# Amplifier.net
KiCad netlist of a schematic drawn in Altium Designer
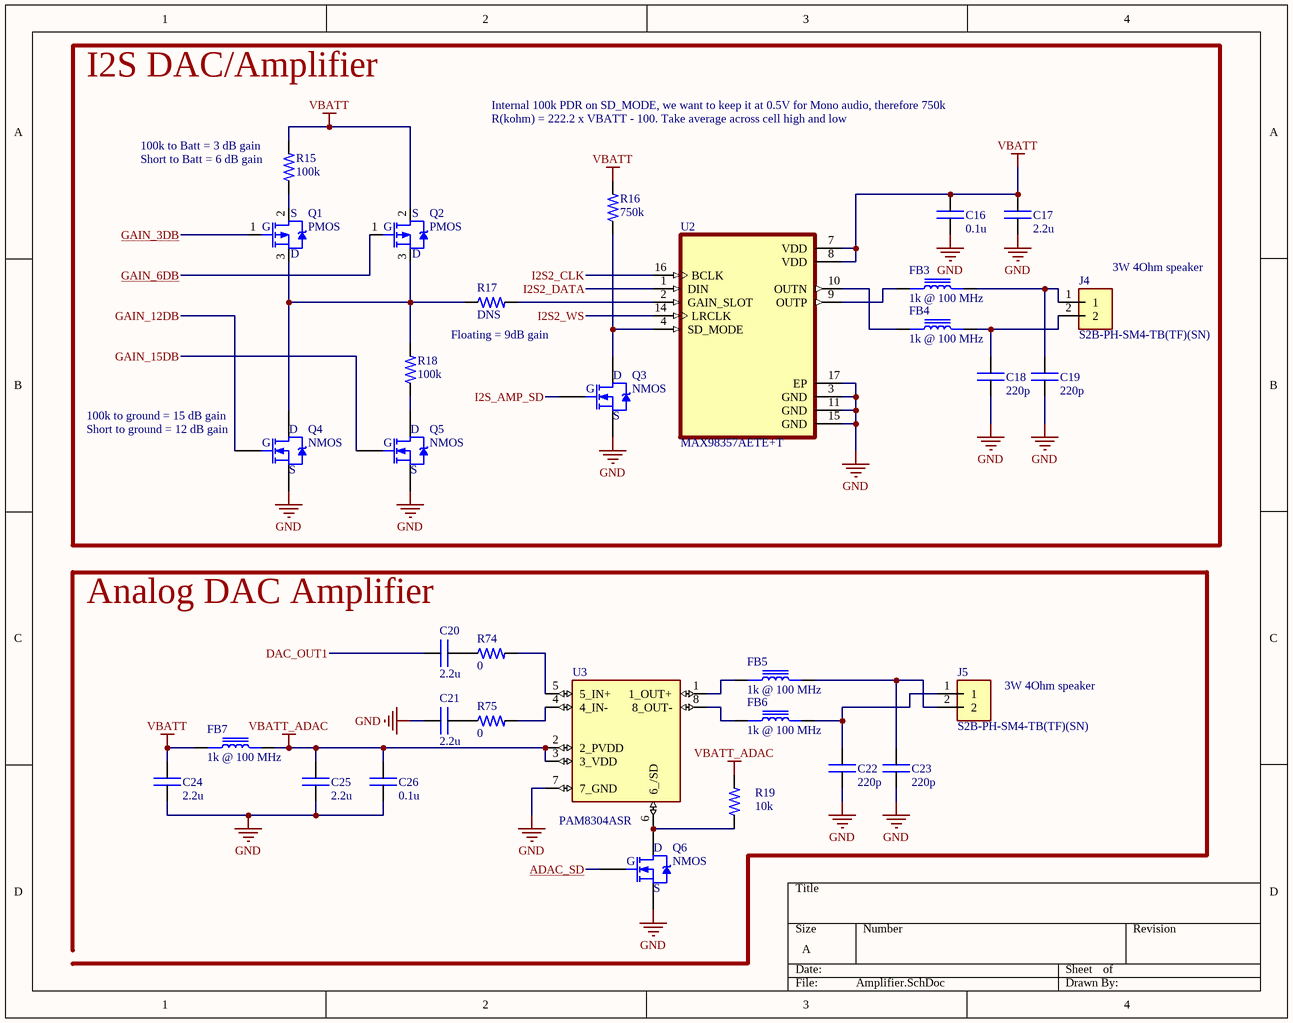
[diagram p0: Amplifier.SchDoc]

(export (version "E")
  (design (tool "Eeschema 10.0.6"))
  (components
    (comp (ref "C16")
      (value "0.1u")
      (footprint "Christmas-2023_Soundboard:0603-CAP")
      (description "Capaicitor")
      (fields (field (name "Comment") "CAP"))
      (libsource (lib "Christmas-2023_Soundboard") (part "CAP"))
    )
    (comp (ref "C17")
      (value "2.2u")
      (footprint "Christmas-2023_Soundboard:0603-CAP")
      (description "Capaicitor")
      (fields (field (name "Comment") "CAP"))
      (libsource (lib "Christmas-2023_Soundboard") (part "CAP"))
    )
    (comp (ref "C18")
      (value "220p")
      (footprint "Christmas-2023_Soundboard:0603-CAP")
      (description "Capaicitor")
      (fields (field (name "Comment") "CAP"))
      (libsource (lib "Christmas-2023_Soundboard") (part "CAP"))
    )
    (comp (ref "C19")
      (value "220p")
      (footprint "Christmas-2023_Soundboard:0603-CAP")
      (description "Capaicitor")
      (fields (field (name "Comment") "CAP"))
      (libsource (lib "Christmas-2023_Soundboard") (part "CAP"))
    )
    (comp (ref "C20")
      (value "2.2u")
      (footprint "Christmas-2023_Soundboard:0603-CAP")
      (description "Capaicitor")
      (fields (field (name "Comment") "CAP"))
      (libsource (lib "Christmas-2023_Soundboard") (part "CAP"))
    )
    (comp (ref "C21")
      (value "2.2u")
      (footprint "Christmas-2023_Soundboard:0603-CAP")
      (description "Capaicitor")
      (fields (field (name "Comment") "CAP"))
      (libsource (lib "Christmas-2023_Soundboard") (part "CAP"))
    )
    (comp (ref "C22")
      (value "220p")
      (footprint "Christmas-2023_Soundboard:0603-CAP")
      (description "Capaicitor")
      (fields (field (name "Comment") "CAP"))
      (libsource (lib "Christmas-2023_Soundboard") (part "CAP"))
    )
    (comp (ref "C23")
      (value "220p")
      (footprint "Christmas-2023_Soundboard:0603-CAP")
      (description "Capaicitor")
      (fields (field (name "Comment") "CAP"))
      (libsource (lib "Christmas-2023_Soundboard") (part "CAP"))
    )
    (comp (ref "C24")
      (value "2.2u")
      (footprint "Christmas-2023_Soundboard:0603-CAP")
      (description "Capaicitor")
      (fields (field (name "Comment") "CAP"))
      (libsource (lib "Christmas-2023_Soundboard") (part "CAP"))
    )
    (comp (ref "C25")
      (value "2.2u")
      (footprint "Christmas-2023_Soundboard:0603-CAP")
      (description "Capaicitor")
      (fields (field (name "Comment") "CAP"))
      (libsource (lib "Christmas-2023_Soundboard") (part "CAP"))
    )
    (comp (ref "C26")
      (value "0.1u")
      (footprint "Christmas-2023_Soundboard:0603-CAP")
      (description "Capaicitor")
      (fields (field (name "Comment") "CAP"))
      (libsource (lib "Christmas-2023_Soundboard") (part "CAP"))
    )
    (comp (ref "FB3")
      (value "1k @ 100 MHz")
      (footprint "Christmas-2023_Soundboard:0603-FB")
      (fields (field (name "MFR") "TDK"))
      (libsource (lib "Christmas-2023_Soundboard") (part "FERRITE BEAD"))
    )
    (comp (ref "FB4")
      (value "1k @ 100 MHz")
      (footprint "Christmas-2023_Soundboard:0603-FB")
      (fields (field (name "MFR") "TDK"))
      (libsource (lib "Christmas-2023_Soundboard") (part "FERRITE BEAD"))
    )
    (comp (ref "FB5")
      (value "1k @ 100 MHz")
      (footprint "Christmas-2023_Soundboard:0603-FB")
      (fields (field (name "MFR") "TDK"))
      (libsource (lib "Christmas-2023_Soundboard") (part "FERRITE BEAD"))
    )
    (comp (ref "FB6")
      (value "1k @ 100 MHz")
      (footprint "Christmas-2023_Soundboard:0603-FB")
      (fields (field (name "MFR") "TDK"))
      (libsource (lib "Christmas-2023_Soundboard") (part "FERRITE BEAD"))
    )
    (comp (ref "FB7")
      (value "1k @ 100 MHz")
      (footprint "Christmas-2023_Soundboard:0603-FB")
      (fields (field (name "MFR") "TDK"))
      (libsource (lib "Christmas-2023_Soundboard") (part "FERRITE BEAD"))
    )
    (comp (ref "J4")
      (value "S2B-PH-SM4-TB(TF)(SN)")
      (footprint "Christmas-2023_Soundboard:JST_PH-2POS-SMT-RA")
      (description "Connector Header Surface Mount, Right Angle 2 position 0.079 (2.00mm)")
      (fields (field (name "MFR") "JST Sales"))
      (libsource (lib "Christmas-2023_Soundboard") (part "JST CONN 2POS PH"))
    )
    (comp (ref "J5")
      (value "S2B-PH-SM4-TB(TF)(SN)")
      (footprint "Christmas-2023_Soundboard:JST_PH-2POS-SMT-RA")
      (description "Connector Header Surface Mount, Right Angle 2 position 0.079 (2.00mm)")
      (fields (field (name "MFR") "JST Sales"))
      (libsource (lib "Christmas-2023_Soundboard") (part "JST CONN 2POS PH"))
    )
    (comp (ref "Q1")
      (value "PMOS")
      (footprint "Christmas-2023_Soundboard:SOT-23")
      (description "P-Channel MOSFET")
      (fields (field (name "MFR") "Diodes Incorporated"))
      (libsource (lib "Christmas-2023_Soundboard") (part "PMOS"))
    )
    (comp (ref "Q2")
      (value "PMOS")
      (footprint "Christmas-2023_Soundboard:SOT-23")
      (description "P-Channel MOSFET")
      (fields (field (name "MFR") "Diodes Incorporated"))
      (libsource (lib "Christmas-2023_Soundboard") (part "PMOS"))
    )
    (comp (ref "Q3")
      (value "NMOS")
      (footprint "Christmas-2023_Soundboard:SOT-23")
      (description "N-Channel MOSFET")
      (fields (field (name "MFR") "Diodes Incorporated"))
      (libsource (lib "Christmas-2023_Soundboard") (part "NMOS"))
    )
    (comp (ref "Q4")
      (value "NMOS")
      (footprint "Christmas-2023_Soundboard:SOT-23")
      (description "N-Channel MOSFET")
      (fields (field (name "MFR") "Diodes Incorporated"))
      (libsource (lib "Christmas-2023_Soundboard") (part "NMOS"))
    )
    (comp (ref "Q5")
      (value "NMOS")
      (footprint "Christmas-2023_Soundboard:SOT-23")
      (description "N-Channel MOSFET")
      (fields (field (name "MFR") "Diodes Incorporated"))
      (libsource (lib "Christmas-2023_Soundboard") (part "NMOS"))
    )
    (comp (ref "Q6")
      (value "NMOS")
      (footprint "Christmas-2023_Soundboard:SOT-23")
      (description "N-Channel MOSFET")
      (fields (field (name "MFR") "Diodes Incorporated"))
      (libsource (lib "Christmas-2023_Soundboard") (part "NMOS"))
    )
    (comp (ref "R15")
      (value "100k")
      (footprint "Christmas-2023_Soundboard:0603-RES")
      (description "Resistor")
      (fields (field (name "Comment") "RES"))
      (libsource (lib "Christmas-2023_Soundboard") (part "RES"))
    )
    (comp (ref "R16")
      (value "750k")
      (footprint "Christmas-2023_Soundboard:0603-RES")
      (description "Resistor")
      (fields (field (name "Comment") "RES"))
      (libsource (lib "Christmas-2023_Soundboard") (part "RES"))
    )
    (comp (ref "R17")
      (value "DNS")
      (footprint "Christmas-2023_Soundboard:0603-RES")
      (description "Resistor")
      (fields (field (name "Comment") "RES"))
      (libsource (lib "Christmas-2023_Soundboard") (part "RES"))
    )
    (comp (ref "R18")
      (value "100k")
      (footprint "Christmas-2023_Soundboard:0603-RES")
      (description "Resistor")
      (fields (field (name "Comment") "RES"))
      (libsource (lib "Christmas-2023_Soundboard") (part "RES"))
    )
    (comp (ref "R19")
      (value "10k")
      (footprint "Christmas-2023_Soundboard:0603-RES")
      (description "Resistor")
      (fields (field (name "Comment") "RES"))
      (libsource (lib "Christmas-2023_Soundboard") (part "RES"))
    )
    (comp (ref "R74")
      (value "0")
      (footprint "Christmas-2023_Soundboard:0603-RES")
      (description "Resistor")
      (fields (field (name "Comment") "RES"))
      (libsource (lib "Christmas-2023_Soundboard") (part "RES"))
    )
    (comp (ref "R75")
      (value "0")
      (footprint "Christmas-2023_Soundboard:0603-RES")
      (description "Resistor")
      (fields (field (name "Comment") "RES"))
      (libsource (lib "Christmas-2023_Soundboard") (part "RES"))
    )
    (comp (ref "U2")
      (value "MAX98357AETE+T")
      (footprint "Christmas-2023_Soundboard:16-WFQFN EXPOSED PAD")
      (description "I2S Audio DAC and amp")
      (fields (field (name "MFR") "Analog Devices"))
      (libsource (lib "Christmas-2023_Soundboard") (part "MAX98357AETE+T"))
    )
    (comp (ref "U3")
      (value "PAM8304ASR")
      (footprint "Christmas-2023_Soundboard:8-TSSOP")
      (description "Amplifier IC 1-Channel (Mono) Class D 8L-MSOP")
      (fields (field (name "MFR") "Diodes Inc."))
      (libsource (lib "Christmas-2023_Soundboard") (part "AMP 3W ANALOG"))
    )
  )
  (nets
    (net (code "1") (name "/ADAC_SD") (class "Default")
      (node (ref "Q6") (pin "1") (pinfunction "G_1") (pintype "passive"))
    )
    (net (code "2") (name "/DAC_OUT1") (class "Default")
      (node (ref "C20") (pin "1") (pinfunction "1_1") (pintype "passive"))
    )
    (net (code "3") (name "/GAIN_3DB") (class "Default")
      (node (ref "Q1") (pin "1") (pinfunction "G_1") (pintype "passive"))
    )
    (net (code "4") (name "/GAIN_6DB") (class "Default")
      (node (ref "Q2") (pin "1") (pinfunction "G_1") (pintype "passive"))
    )
    (net (code "5") (name "/GAIN_12DB") (class "Default")
      (node (ref "Q4") (pin "1") (pinfunction "G_1") (pintype "passive"))
    )
    (net (code "6") (name "/GAIN_15DB") (class "Default")
      (node (ref "Q5") (pin "1") (pinfunction "G_1") (pintype "passive"))
    )
    (net (code "7") (name "/I2S2_CLK") (class "Default")
      (node (ref "U2") (pin "16") (pinfunction "BCLK_16") (pintype "input"))
    )
    (net (code "8") (name "/I2S2_DATA") (class "Default")
      (node (ref "U2") (pin "1") (pinfunction "DIN_1") (pintype "input"))
    )
    (net (code "9") (name "/I2S2_WS") (class "Default")
      (node (ref "U2") (pin "14") (pinfunction "LRCLK_14") (pintype "input"))
    )
    (net (code "10") (name "/I2S_AMP_SD") (class "Default")
      (node (ref "Q3") (pin "1") (pinfunction "G_1") (pintype "passive"))
    )
    (net (code "11") (name "GND") (class "Default")
      (node (ref "C16") (pin "1") (pinfunction "1_1") (pintype "passive"))
      (node (ref "C17") (pin "1") (pinfunction "1_1") (pintype "passive"))
      (node (ref "C18") (pin "1") (pinfunction "1_1") (pintype "passive"))
      (node (ref "C19") (pin "1") (pinfunction "1_1") (pintype "passive"))
      (node (ref "C21") (pin "1") (pinfunction "1_1") (pintype "passive"))
      (node (ref "C22") (pin "1") (pinfunction "1_1") (pintype "passive"))
      (node (ref "C23") (pin "1") (pinfunction "1_1") (pintype "passive"))
      (node (ref "C24") (pin "1") (pinfunction "1_1") (pintype "passive"))
      (node (ref "C25") (pin "1") (pinfunction "1_1") (pintype "passive"))
      (node (ref "C26") (pin "1") (pinfunction "1_1") (pintype "passive"))
      (node (ref "Q3") (pin "2") (pinfunction "S_2") (pintype "passive"))
      (node (ref "Q4") (pin "2") (pinfunction "S_2") (pintype "passive"))
      (node (ref "Q5") (pin "2") (pinfunction "S_2") (pintype "passive"))
      (node (ref "Q6") (pin "2") (pinfunction "S_2") (pintype "passive"))
      (node (ref "U2") (pin "11") (pinfunction "GND_11") (pintype "power_in"))
      (node (ref "U2") (pin "15") (pinfunction "GND_15") (pintype "power_in"))
      (node (ref "U2") (pin "17") (pinfunction "EP_17") (pintype "power_in"))
      (node (ref "U2") (pin "3") (pinfunction "GND_3") (pintype "power_in"))
      (node (ref "U3") (pin "7") (pinfunction "7_GND_7") (pintype "bidirectional"))
    )
    (net (code "12") (name "Net-(C18-Pad2)") (class "Default")
      (node (ref "C18") (pin "2") (pinfunction "2_2") (pintype "passive"))
      (node (ref "FB4") (pin "2") (pinfunction "2_2") (pintype "passive"))
      (node (ref "J4") (pin "2") (pinfunction "2_2") (pintype "passive"))
    )
    (net (code "13") (name "Net-(C19-Pad2)") (class "Default")
      (node (ref "C19") (pin "2") (pinfunction "2_2") (pintype "passive"))
      (node (ref "FB3") (pin "2") (pinfunction "2_2") (pintype "passive"))
      (node (ref "J4") (pin "1") (pinfunction "1_1") (pintype "passive"))
    )
    (net (code "14") (name "Net-(C20-Pad2)") (class "Default")
      (node (ref "C20") (pin "2") (pinfunction "2_2") (pintype "passive"))
      (node (ref "R74") (pin "1") (pinfunction "1_1") (pintype "passive"))
    )
    (net (code "15") (name "Net-(C21-Pad2)") (class "Default")
      (node (ref "C21") (pin "2") (pinfunction "2_2") (pintype "passive"))
      (node (ref "R75") (pin "1") (pinfunction "1_1") (pintype "passive"))
    )
    (net (code "16") (name "Net-(C22-Pad2)") (class "Default")
      (node (ref "C22") (pin "2") (pinfunction "2_2") (pintype "passive"))
      (node (ref "FB6") (pin "2") (pinfunction "2_2") (pintype "passive"))
      (node (ref "J5") (pin "1") (pinfunction "1_1") (pintype "passive"))
    )
    (net (code "17") (name "Net-(C23-Pad2)") (class "Default")
      (node (ref "C23") (pin "2") (pinfunction "2_2") (pintype "passive"))
      (node (ref "FB5") (pin "2") (pinfunction "2_2") (pintype "passive"))
      (node (ref "J5") (pin "2") (pinfunction "2_2") (pintype "passive"))
    )
    (net (code "18") (name "Net-(Q1-D)") (class "Default")
      (node (ref "Q1") (pin "2") (pinfunction "D_2") (pintype "passive"))
      (node (ref "R15") (pin "1") (pinfunction "1_1") (pintype "passive"))
    )
    (net (code "19") (name "Net-(Q1-S)") (class "Default")
      (node (ref "Q1") (pin "3") (pinfunction "S_3") (pintype "passive"))
      (node (ref "Q2") (pin "3") (pinfunction "S_3") (pintype "passive"))
      (node (ref "Q4") (pin "3") (pinfunction "D_3") (pintype "passive"))
      (node (ref "R17") (pin "1") (pinfunction "1_1") (pintype "passive"))
      (node (ref "R18") (pin "2") (pinfunction "2_2") (pintype "passive"))
    )
    (net (code "20") (name "Net-(Q3-D)") (class "Default")
      (node (ref "Q3") (pin "3") (pinfunction "D_3") (pintype "passive"))
      (node (ref "R16") (pin "1") (pinfunction "1_1") (pintype "passive"))
      (node (ref "U2") (pin "4") (pinfunction "SD_MODE_4") (pintype "input"))
    )
    (net (code "21") (name "Net-(Q5-D)") (class "Default")
      (node (ref "Q5") (pin "3") (pinfunction "D_3") (pintype "passive"))
      (node (ref "R18") (pin "1") (pinfunction "1_1") (pintype "passive"))
    )
    (net (code "22") (name "Net-(Q6-D)") (class "Default")
      (node (ref "Q6") (pin "3") (pinfunction "D_3") (pintype "passive"))
      (node (ref "R19") (pin "1") (pinfunction "1_1") (pintype "passive"))
      (node (ref "U3") (pin "6") (pinfunction "6_/SD_6") (pintype "bidirectional"))
    )
    (net (code "23") (name "Net-(U2-GAIN_SLOT)") (class "Default")
      (node (ref "R17") (pin "2") (pinfunction "2_2") (pintype "passive"))
      (node (ref "U2") (pin "2") (pinfunction "GAIN_SLOT_2") (pintype "input"))
    )
    (net (code "24") (name "Net-(U2-OUTN)") (class "Default")
      (node (ref "FB4") (pin "1") (pinfunction "1_1") (pintype "passive"))
      (node (ref "U2") (pin "10") (pinfunction "OUTN_10") (pintype "output"))
    )
    (net (code "25") (name "Net-(U2-OUTP)") (class "Default")
      (node (ref "FB3") (pin "1") (pinfunction "1_1") (pintype "passive"))
      (node (ref "U2") (pin "9") (pinfunction "OUTP_9") (pintype "output"))
    )
    (net (code "26") (name "Net-(U3-1_OUT+)") (class "Default")
      (node (ref "FB5") (pin "1") (pinfunction "1_1") (pintype "passive"))
      (node (ref "U3") (pin "1") (pinfunction "1_OUT+_1") (pintype "bidirectional"))
    )
    (net (code "27") (name "Net-(U3-4_IN-)") (class "Default")
      (node (ref "R75") (pin "2") (pinfunction "2_2") (pintype "passive"))
      (node (ref "U3") (pin "4") (pinfunction "4_IN-_4") (pintype "bidirectional"))
    )
    (net (code "28") (name "Net-(U3-5_IN+)") (class "Default")
      (node (ref "R74") (pin "2") (pinfunction "2_2") (pintype "passive"))
      (node (ref "U3") (pin "5") (pinfunction "5_IN+_5") (pintype "bidirectional"))
    )
    (net (code "29") (name "Net-(U3-8_OUT-)") (class "Default")
      (node (ref "FB6") (pin "1") (pinfunction "1_1") (pintype "passive"))
      (node (ref "U3") (pin "8") (pinfunction "8_OUT-_8") (pintype "bidirectional"))
    )
    (net (code "30") (name "VBATT") (class "Default")
      (node (ref "C16") (pin "2") (pinfunction "2_2") (pintype "passive"))
      (node (ref "C17") (pin "2") (pinfunction "2_2") (pintype "passive"))
      (node (ref "C24") (pin "2") (pinfunction "2_2") (pintype "passive"))
      (node (ref "FB7") (pin "1") (pinfunction "1_1") (pintype "passive"))
      (node (ref "Q2") (pin "2") (pinfunction "D_2") (pintype "passive"))
      (node (ref "R15") (pin "2") (pinfunction "2_2") (pintype "passive"))
      (node (ref "R16") (pin "2") (pinfunction "2_2") (pintype "passive"))
      (node (ref "U2") (pin "7") (pinfunction "VDD_7") (pintype "power_in"))
      (node (ref "U2") (pin "8") (pinfunction "VDD_8") (pintype "power_in"))
    )
    (net (code "31") (name "VBATT_ADAC") (class "Default")
      (node (ref "C25") (pin "2") (pinfunction "2_2") (pintype "passive"))
      (node (ref "C26") (pin "2") (pinfunction "2_2") (pintype "passive"))
      (node (ref "FB7") (pin "2") (pinfunction "2_2") (pintype "passive"))
      (node (ref "R19") (pin "2") (pinfunction "2_2") (pintype "passive"))
      (node (ref "U3") (pin "2") (pinfunction "2_PVDD_2") (pintype "bidirectional"))
      (node (ref "U3") (pin "3") (pinfunction "3_VDD_3") (pintype "bidirectional"))
    )
  )
)
